# V2_Layout.net
KiCad netlist of a schematic drawn in EAGLE
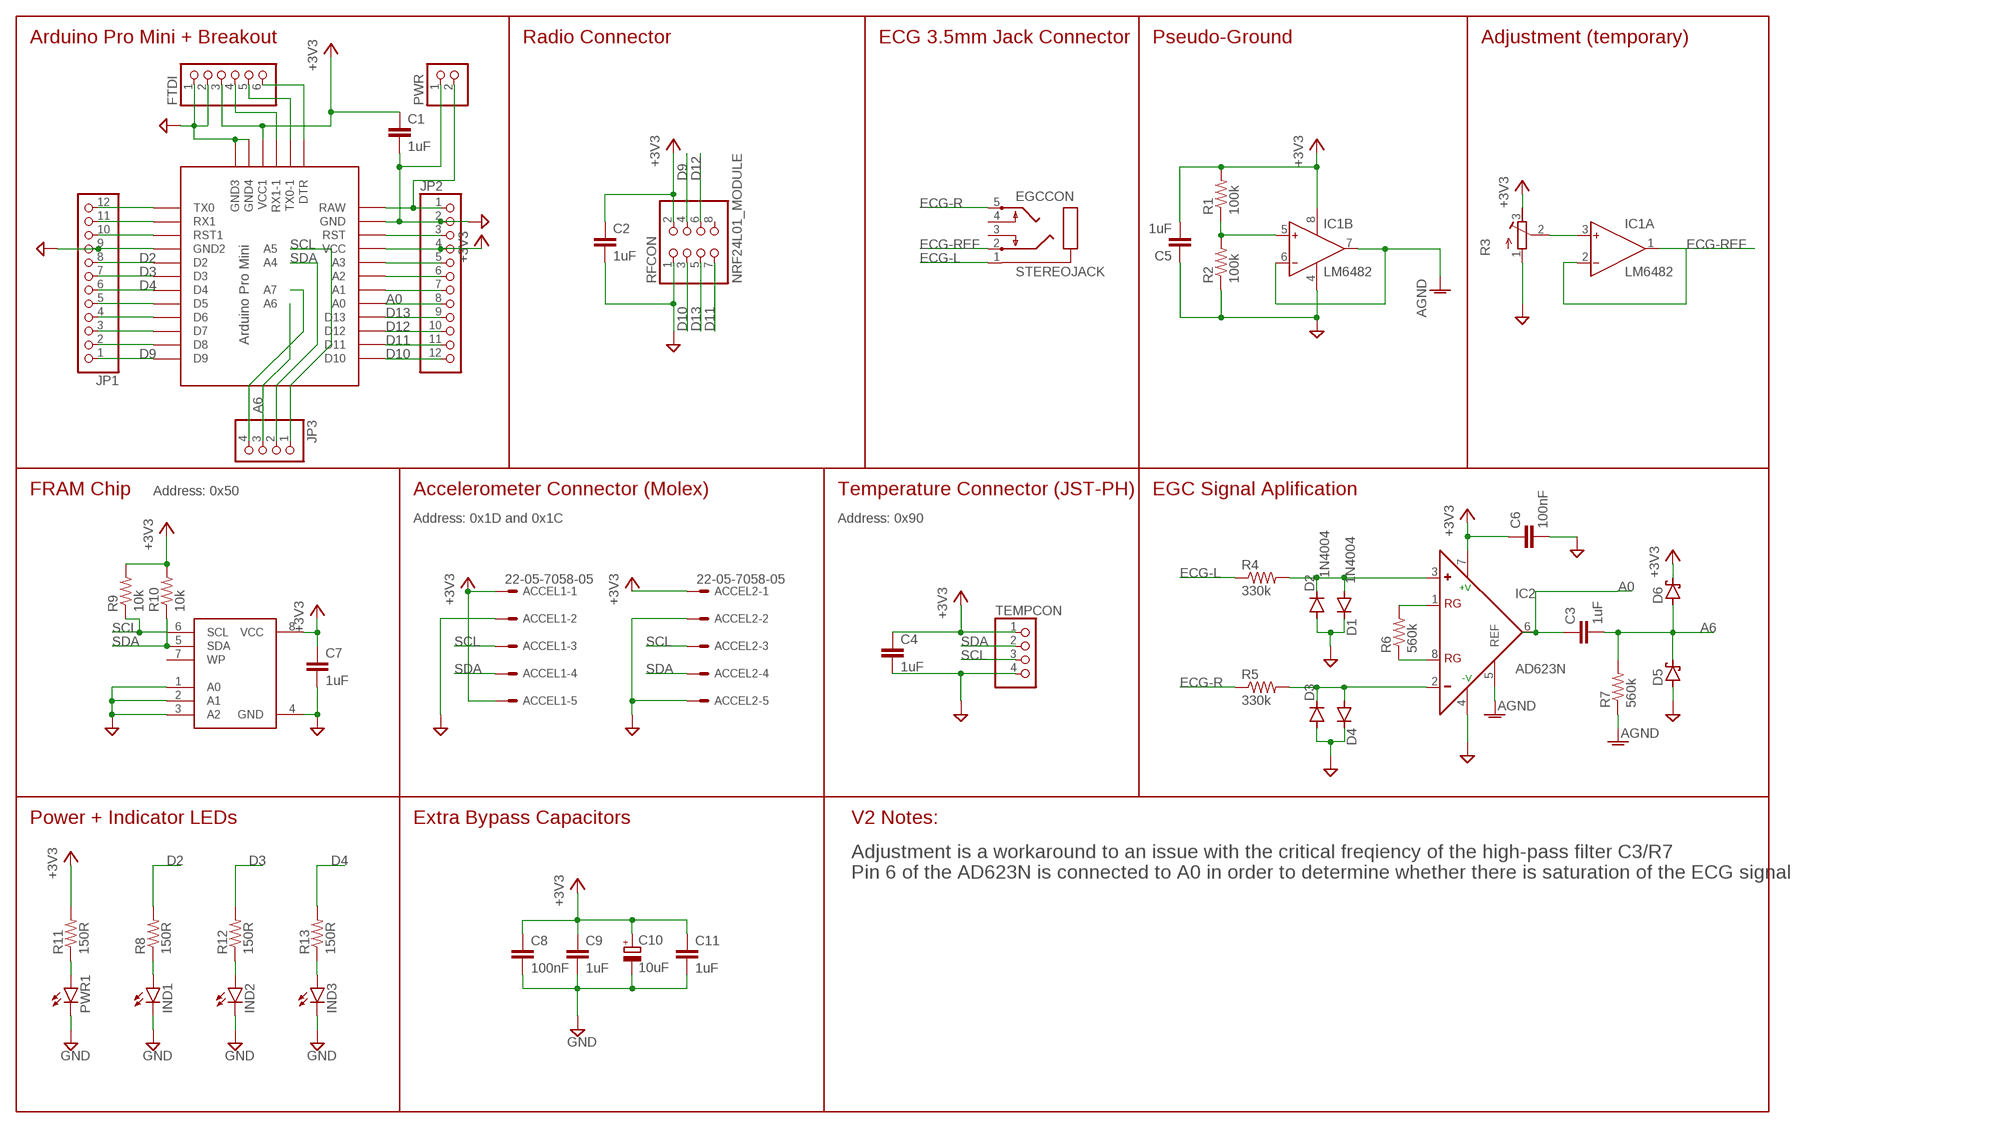
[diagram p0: schematic, sheet 1]

(export (version "E")
  (design (tool "Eeschema 10.0.6"))
  (components
    (comp (ref "ACCEL1")
      (value "22-05-7058-05")
      (footprint "eagle-import:7395-05")
      (fields (field (name "MF") "MOLEX"))
      (libsource (lib "eagle-import") (part "22-?-0505-7058"))
    )
    (comp (ref "ACCEL2")
      (value "22-05-7058-05")
      (footprint "eagle-import:7395-05")
      (fields (field (name "MF") "MOLEX"))
      (libsource (lib "eagle-import") (part "22-?-0505-7058"))
    )
    (comp (ref "C1")
      (value "1uF")
      (footprint "eagle-import:C0603")
      (libsource (lib "eagle-import") (part "C-EUC0603"))
    )
    (comp (ref "C2")
      (value "1uF")
      (footprint "eagle-import:C0603")
      (libsource (lib "eagle-import") (part "C-EUC0603"))
    )
    (comp (ref "C3")
      (value "1uF")
      (footprint "eagle-import:C0603")
      (libsource (lib "eagle-import") (part "C-EUC0603"))
    )
    (comp (ref "C4")
      (value "1uF")
      (footprint "eagle-import:C0603")
      (libsource (lib "eagle-import") (part "C-EUC0603"))
    )
    (comp (ref "C5")
      (value "1uF")
      (footprint "eagle-import:C0603")
      (libsource (lib "eagle-import") (part "C-EUC0603"))
    )
    (comp (ref "C6")
      (value "100nF")
      (footprint "eagle-import:C0603")
      (libsource (lib "eagle-import") (part "C-EUC0603"))
    )
    (comp (ref "C7")
      (value "1uF")
      (footprint "eagle-import:C0603")
      (libsource (lib "eagle-import") (part "C-EUC0603"))
    )
    (comp (ref "C8")
      (value "100nF")
      (footprint "eagle-import:C025-030X050")
      (libsource (lib "eagle-import") (part "C-EU025-030X050"))
    )
    (comp (ref "C9")
      (value "1uF")
      (footprint "eagle-import:C025-030X050")
      (libsource (lib "eagle-import") (part "C-EU025-030X050"))
    )
    (comp (ref "C10")
      (value "10uF")
      (footprint "eagle-import:TAP5-45")
      (libsource (lib "eagle-import") (part "CPOL-EUTAP5-45"))
    )
    (comp (ref "C11")
      (value "1uF")
      (footprint "eagle-import:C025-030X050")
      (libsource (lib "eagle-import") (part "C-EU025-030X050"))
    )
    (comp (ref "D1")
      (value "1N4004")
      (footprint "eagle-import:DO41-10")
      (libsource (lib "eagle-import") (part "1N4004"))
    )
    (comp (ref "D2")
      (value "1N4004")
      (footprint "eagle-import:DO41-10")
      (libsource (lib "eagle-import") (part "1N4004"))
    )
    (comp (ref "D3")
      (value "1N4004")
      (footprint "eagle-import:DO41-10")
      (libsource (lib "eagle-import") (part "1N4004"))
    )
    (comp (ref "D4")
      (value "1N4004")
      (footprint "eagle-import:DO41-10")
      (libsource (lib "eagle-import") (part "1N4004"))
    )
    (comp (ref "D5")
      (value "SCHOTTKY-DIODEDO35-7")
      (footprint "eagle-import:DO35-7")
      (libsource (lib "eagle-import") (part "SCHOTTKY-DIODEDO35-7"))
    )
    (comp (ref "D6")
      (value "SCHOTTKY-DIODEDO35-7")
      (footprint "eagle-import:DO35-7")
      (libsource (lib "eagle-import") (part "SCHOTTKY-DIODEDO35-7"))
    )
    (comp (ref "EGCCON")
      (value "STEREOJACK")
      (footprint "eagle-import:STX3100")
      (libsource (lib "eagle-import") (part "STEREOJACK"))
    )
    (comp (ref "FTDI")
      (value "PINHD-1X6")
      (footprint "eagle-import:1X06")
      (libsource (lib "eagle-import") (part "PINHD-1X6"))
    )
    (comp (ref "IC1")
      (value "LM6482")
      (footprint "eagle-import:DIL08")
      (fields (field (name "MF") "ALTERA CORPORATION") (field (name "MPN") "AD826ANZ"))
      (libsource (lib "eagle-import") (part "AD826N"))
    )
    (comp (ref "IC2")
      (value "AD623N")
      (footprint "eagle-import:DIL08")
      (fields (field (name "MF") "ALTERA CORPORATION") (field (name "MPN") "AD623ANZ"))
      (libsource (lib "eagle-import") (part "AD623N"))
    )
    (comp (ref "IND1")
      (value "LEDCHIPLED_0805")
      (footprint "eagle-import:CHIPLED_0805")
      (libsource (lib "eagle-import") (part "LEDCHIPLED_0805"))
    )
    (comp (ref "IND2")
      (value "LEDCHIPLED_0805")
      (footprint "eagle-import:CHIPLED_0805")
      (libsource (lib "eagle-import") (part "LEDCHIPLED_0805"))
    )
    (comp (ref "IND3")
      (value "LEDCHIPLED_0805")
      (footprint "eagle-import:CHIPLED_0805")
      (libsource (lib "eagle-import") (part "LEDCHIPLED_0805"))
    )
    (comp (ref "JP1")
      (value "PINHD-1X12")
      (footprint "eagle-import:1X12")
      (libsource (lib "eagle-import") (part "PINHD-1X12"))
    )
    (comp (ref "JP2")
      (value "PINHD-1X12")
      (footprint "eagle-import:1X12")
      (libsource (lib "eagle-import") (part "PINHD-1X12"))
    )
    (comp (ref "JP3")
      (value "PINHD-1X4")
      (footprint "eagle-import:1X04")
      (libsource (lib "eagle-import") (part "pinhead_325_PINHD-1X4"))
    )
    (comp (ref "PWR")
      (value "PINHD-1X2")
      (footprint "eagle-import:1X02")
      (libsource (lib "eagle-import") (part "PINHD-1X2"))
    )
    (comp (ref "PWR1")
      (value "LEDCHIPLED_0805")
      (footprint "eagle-import:CHIPLED_0805")
      (libsource (lib "eagle-import") (part "LEDCHIPLED_0805"))
    )
    (comp (ref "R1")
      (value "100k")
      (footprint "eagle-import:R0603")
      (libsource (lib "eagle-import") (part "R-US_R0603"))
    )
    (comp (ref "R2")
      (value "100k")
      (footprint "eagle-import:R0603")
      (libsource (lib "eagle-import") (part "R-US_R0603"))
    )
    (comp (ref "R3")
      (value "R-TRIMM64P")
      (footprint "eagle-import:RTRIM64P")
      (libsource (lib "eagle-import") (part "R-TRIMM64P"))
    )
    (comp (ref "R4")
      (value "330k")
      (footprint "eagle-import:R0603")
      (libsource (lib "eagle-import") (part "R-US_R0603"))
    )
    (comp (ref "R5")
      (value "330k")
      (footprint "eagle-import:R0603")
      (libsource (lib "eagle-import") (part "R-US_R0603"))
    )
    (comp (ref "R6")
      (value "560k")
      (footprint "eagle-import:R0603")
      (libsource (lib "eagle-import") (part "R-US_R0603"))
    )
    (comp (ref "R7")
      (value "560k")
      (footprint "eagle-import:R0603")
      (libsource (lib "eagle-import") (part "R-US_R0603"))
    )
    (comp (ref "R8")
      (value "150R")
      (footprint "eagle-import:R0603")
      (libsource (lib "eagle-import") (part "R-US_R0603"))
    )
    (comp (ref "R9")
      (value "10k")
      (footprint "eagle-import:R0603")
      (libsource (lib "eagle-import") (part "R-US_R0603"))
    )
    (comp (ref "R10")
      (value "10k")
      (footprint "eagle-import:R0603")
      (libsource (lib "eagle-import") (part "R-US_R0603"))
    )
    (comp (ref "R11")
      (value "150R")
      (footprint "eagle-import:R0603")
      (libsource (lib "eagle-import") (part "R-US_R0603"))
    )
    (comp (ref "R12")
      (value "150R")
      (footprint "eagle-import:R0603")
      (libsource (lib "eagle-import") (part "R-US_R0603"))
    )
    (comp (ref "R13")
      (value "150R")
      (footprint "eagle-import:R0603")
      (libsource (lib "eagle-import") (part "R-US_R0603"))
    )
    (comp (ref "RFCON")
      (value "NRF24L01_MODULE")
      (footprint "eagle-import:2X04")
      (libsource (lib "eagle-import") (part "NRF24L01_MODULE"))
    )
    (comp (ref "TEMPCON")
      (value "PINHD-1X4M")
      (footprint "eagle-import:1X04M")
      (libsource (lib "eagle-import") (part "PINHD-1X4M"))
    )
    (comp (ref "U$1")
      (value "PRO-MINI-2")
      (footprint "eagle-import:PRO-MINI-2")
      (libsource (lib "eagle-import") (part "PRO-MINI-2"))
    )
    (comp (ref "U2")
      (value "MB85RC256VPF-G-JNERE2")
      (footprint "eagle-import:SOIC8")
      (libsource (lib "eagle-import") (part "MB85RC256VPF-G-JNERE2"))
    )
  )
  (nets
    (net (code "1") (name "+3V3") (class "Default")
      (node (ref "ACCEL1") (pin "1") (pinfunction "S_1") (pintype "passive"))
      (node (ref "ACCEL1") (pin "5") (pinfunction "S_5") (pintype "passive"))
      (node (ref "ACCEL2") (pin "1") (pinfunction "S_1") (pintype "passive"))
      (node (ref "C1") (pin "1") (pinfunction "1_1") (pintype "passive"))
      (node (ref "C10") (pin "+") (pinfunction "+_+") (pintype "passive"))
      (node (ref "C11") (pin "1") (pinfunction "1_1") (pintype "passive"))
      (node (ref "C2") (pin "1") (pinfunction "1_1") (pintype "passive"))
      (node (ref "C4") (pin "1") (pinfunction "1_1") (pintype "passive"))
      (node (ref "C5") (pin "2") (pinfunction "2_2") (pintype "passive"))
      (node (ref "C6") (pin "1") (pinfunction "1_1") (pintype "passive"))
      (node (ref "C7") (pin "1") (pinfunction "1_1") (pintype "passive"))
      (node (ref "C8") (pin "1") (pinfunction "1_1") (pintype "passive"))
      (node (ref "C9") (pin "1") (pinfunction "1_1") (pintype "passive"))
      (node (ref "D6") (pin "C") (pinfunction "C_C") (pintype "passive"))
      (node (ref "FTDI") (pin "3") (pinfunction "3_3") (pintype "passive"))
      (node (ref "IC1") (pin "8") (pinfunction "V+_8") (pintype "power_in"))
      (node (ref "IC2") (pin "7") (pinfunction "+V_7") (pintype "power_in"))
      (node (ref "JP2") (pin "4") (pinfunction "4_4") (pintype "passive"))
      (node (ref "R1") (pin "2") (pinfunction "2_2") (pintype "passive"))
      (node (ref "R10") (pin "2") (pinfunction "2_2") (pintype "passive"))
      (node (ref "R11") (pin "2") (pinfunction "2_2") (pintype "passive"))
      (node (ref "R3") (pin "3") (pinfunction "E_3") (pintype "passive"))
      (node (ref "R9") (pin "2") (pinfunction "2_2") (pintype "passive"))
      (node (ref "RFCON") (pin "2") (pinfunction "2_2") (pintype "passive"))
      (node (ref "TEMPCON") (pin "1") (pinfunction "1_1") (pintype "passive"))
      (node (ref "U$1") (pin "VCC") (pinfunction "VCC_VCC") (pintype "bidirectional"))
      (node (ref "U$1") (pin "VCC1") (pinfunction "VCC1_VCC1") (pintype "bidirectional"))
      (node (ref "U2") (pin "8") (pinfunction "VCC_8") (pintype "bidirectional"))
    )
    (net (code "2") (name "/A0") (class "Default")
      (node (ref "C3") (pin "1") (pinfunction "1_1") (pintype "passive"))
      (node (ref "IC2") (pin "6") (pinfunction "OUT_6") (pintype "output"))
      (node (ref "JP2") (pin "8") (pinfunction "8_8") (pintype "passive"))
      (node (ref "U$1") (pin "A3") (pinfunction "A0_A3") (pintype "bidirectional"))
    )
    (net (code "3") (name "/A6") (class "Default")
      (node (ref "C3") (pin "2") (pinfunction "2_2") (pintype "passive"))
      (node (ref "D5") (pin "C") (pinfunction "C_C") (pintype "passive"))
      (node (ref "D6") (pin "A") (pinfunction "A_A") (pintype "passive"))
      (node (ref "JP3") (pin "3") (pinfunction "3_3") (pintype "passive"))
      (node (ref "R7") (pin "2") (pinfunction "2_2") (pintype "passive"))
      (node (ref "U$1") (pin "A6") (pinfunction "A6_A6") (pintype "bidirectional"))
    )
    (net (code "4") (name "/D2") (class "Default")
      (node (ref "JP1") (pin "8") (pinfunction "8_8") (pintype "passive"))
      (node (ref "R8") (pin "2") (pinfunction "2_2") (pintype "passive"))
      (node (ref "U$1") (pin "D2") (pinfunction "D2_D2") (pintype "bidirectional"))
    )
    (net (code "5") (name "/D3") (class "Default")
      (node (ref "JP1") (pin "7") (pinfunction "7_7") (pintype "passive"))
      (node (ref "R12") (pin "2") (pinfunction "2_2") (pintype "passive"))
      (node (ref "U$1") (pin "D3") (pinfunction "D3_D3") (pintype "bidirectional"))
    )
    (net (code "6") (name "/D4") (class "Default")
      (node (ref "JP1") (pin "6") (pinfunction "6_6") (pintype "passive"))
      (node (ref "R13") (pin "2") (pinfunction "2_2") (pintype "passive"))
      (node (ref "U$1") (pin "D4") (pinfunction "D4_D4") (pintype "bidirectional"))
    )
    (net (code "7") (name "/D9") (class "Default")
      (node (ref "JP1") (pin "1") (pinfunction "1_1") (pintype "passive"))
      (node (ref "RFCON") (pin "4") (pinfunction "4_4") (pintype "passive"))
      (node (ref "U$1") (pin "D9") (pinfunction "D9_D9") (pintype "bidirectional"))
    )
    (net (code "8") (name "/D10") (class "Default")
      (node (ref "JP2") (pin "12") (pinfunction "12_12") (pintype "passive"))
      (node (ref "RFCON") (pin "3") (pinfunction "3_3") (pintype "passive"))
      (node (ref "U$1") (pin "D10") (pinfunction "D10_D10") (pintype "bidirectional"))
    )
    (net (code "9") (name "/D11") (class "Default")
      (node (ref "JP2") (pin "11") (pinfunction "11_11") (pintype "passive"))
      (node (ref "RFCON") (pin "7") (pinfunction "7_7") (pintype "passive"))
      (node (ref "U$1") (pin "D11") (pinfunction "D11_D11") (pintype "bidirectional"))
    )
    (net (code "10") (name "/D12") (class "Default")
      (node (ref "JP2") (pin "10") (pinfunction "10_10") (pintype "passive"))
      (node (ref "RFCON") (pin "6") (pinfunction "6_6") (pintype "passive"))
      (node (ref "U$1") (pin "D12") (pinfunction "D12_D12") (pintype "bidirectional"))
    )
    (net (code "11") (name "/D13") (class "Default")
      (node (ref "JP2") (pin "9") (pinfunction "9_9") (pintype "passive"))
      (node (ref "RFCON") (pin "5") (pinfunction "5_5") (pintype "passive"))
      (node (ref "U$1") (pin "D13") (pinfunction "D13_D13") (pintype "bidirectional"))
    )
    (net (code "12") (name "/ECG-L") (class "Default")
      (node (ref "EGCCON") (pin "1") (pinfunction "1_1") (pintype "passive"))
      (node (ref "R4") (pin "1") (pinfunction "1_1") (pintype "passive"))
    )
    (net (code "13") (name "/ECG-R") (class "Default")
      (node (ref "EGCCON") (pin "5") (pinfunction "5_5") (pintype "passive"))
      (node (ref "R5") (pin "1") (pinfunction "1_1") (pintype "passive"))
    )
    (net (code "14") (name "/ECG-REF") (class "Default")
      (node (ref "EGCCON") (pin "2") (pinfunction "2_2") (pintype "passive"))
      (node (ref "IC1") (pin "1") (pinfunction "OUT_1") (pintype "output"))
      (node (ref "IC1") (pin "2") (pinfunction "IN-_2") (pintype "input"))
    )
    (net (code "15") (name "/SCL") (class "Default")
      (node (ref "ACCEL1") (pin "3") (pinfunction "S_3") (pintype "passive"))
      (node (ref "ACCEL2") (pin "3") (pinfunction "S_3") (pintype "passive"))
      (node (ref "JP3") (pin "1") (pinfunction "1_1") (pintype "passive"))
      (node (ref "R9") (pin "1") (pinfunction "1_1") (pintype "passive"))
      (node (ref "TEMPCON") (pin "3") (pinfunction "3_3") (pintype "passive"))
      (node (ref "U$1") (pin "A5") (pinfunction "A5_A5") (pintype "bidirectional"))
      (node (ref "U2") (pin "6") (pinfunction "SCL_6") (pintype "bidirectional"))
    )
    (net (code "16") (name "/SDA") (class "Default")
      (node (ref "ACCEL1") (pin "4") (pinfunction "S_4") (pintype "passive"))
      (node (ref "ACCEL2") (pin "4") (pinfunction "S_4") (pintype "passive"))
      (node (ref "JP3") (pin "2") (pinfunction "2_2") (pintype "passive"))
      (node (ref "R10") (pin "1") (pinfunction "1_1") (pintype "passive"))
      (node (ref "TEMPCON") (pin "2") (pinfunction "2_2") (pintype "passive"))
      (node (ref "U$1") (pin "A4") (pinfunction "A4_A4") (pintype "bidirectional"))
      (node (ref "U2") (pin "5") (pinfunction "SDA_5") (pintype "bidirectional"))
    )
    (net (code "17") (name "AGND") (class "Default")
      (node (ref "IC1") (pin "6") (pinfunction "IN-_6") (pintype "input"))
      (node (ref "IC1") (pin "7") (pinfunction "OUT_7") (pintype "output"))
      (node (ref "IC2") (pin "5") (pinfunction "REF_5") (pintype "passive"))
      (node (ref "R7") (pin "1") (pinfunction "1_1") (pintype "passive"))
    )
    (net (code "18") (name "GND") (class "Default")
      (node (ref "ACCEL1") (pin "2") (pinfunction "S_2") (pintype "passive"))
      (node (ref "ACCEL2") (pin "2") (pinfunction "S_2") (pintype "passive"))
      (node (ref "ACCEL2") (pin "5") (pinfunction "S_5") (pintype "passive"))
      (node (ref "C1") (pin "2") (pinfunction "2_2") (pintype "passive"))
      (node (ref "C10") (pin "-") (pinfunction "-_-") (pintype "passive"))
      (node (ref "C11") (pin "2") (pinfunction "2_2") (pintype "passive"))
      (node (ref "C2") (pin "2") (pinfunction "2_2") (pintype "passive"))
      (node (ref "C4") (pin "2") (pinfunction "2_2") (pintype "passive"))
      (node (ref "C5") (pin "1") (pinfunction "1_1") (pintype "passive"))
      (node (ref "C6") (pin "2") (pinfunction "2_2") (pintype "passive"))
      (node (ref "C7") (pin "2") (pinfunction "2_2") (pintype "passive"))
      (node (ref "C8") (pin "2") (pinfunction "2_2") (pintype "passive"))
      (node (ref "C9") (pin "2") (pinfunction "2_2") (pintype "passive"))
      (node (ref "D1") (pin "C") (pinfunction "C_C") (pintype "passive"))
      (node (ref "D2") (pin "A") (pinfunction "A_A") (pintype "passive"))
      (node (ref "D3") (pin "A") (pinfunction "A_A") (pintype "passive"))
      (node (ref "D4") (pin "C") (pinfunction "C_C") (pintype "passive"))
      (node (ref "D5") (pin "A") (pinfunction "A_A") (pintype "passive"))
      (node (ref "FTDI") (pin "1") (pinfunction "1_1") (pintype "passive"))
      (node (ref "FTDI") (pin "2") (pinfunction "2_2") (pintype "passive"))
      (node (ref "IC1") (pin "4") (pinfunction "V-_4") (pintype "power_in"))
      (node (ref "IC2") (pin "4") (pinfunction "-V_4") (pintype "power_in"))
      (node (ref "IND1") (pin "C") (pinfunction "C_C") (pintype "passive"))
      (node (ref "IND2") (pin "C") (pinfunction "C_C") (pintype "passive"))
      (node (ref "IND3") (pin "C") (pinfunction "C_C") (pintype "passive"))
      (node (ref "JP1") (pin "9") (pinfunction "9_9") (pintype "passive"))
      (node (ref "JP2") (pin "2") (pinfunction "2_2") (pintype "passive"))
      (node (ref "PWR") (pin "1") (pinfunction "1_1") (pintype "passive"))
      (node (ref "PWR1") (pin "C") (pinfunction "C_C") (pintype "passive"))
      (node (ref "R2") (pin "1") (pinfunction "1_1") (pintype "passive"))
      (node (ref "R3") (pin "1") (pinfunction "A_1") (pintype "passive"))
      (node (ref "RFCON") (pin "1") (pinfunction "1_1") (pintype "passive"))
      (node (ref "TEMPCON") (pin "4") (pinfunction "4_4") (pintype "passive"))
      (node (ref "U$1") (pin "GND") (pinfunction "GND_GND") (pintype "bidirectional"))
      (node (ref "U$1") (pin "GND1") (pinfunction "GND2_GND1") (pintype "bidirectional"))
      (node (ref "U$1") (pin "GND2") (pinfunction "GND3_GND2") (pintype "bidirectional"))
      (node (ref "U$1") (pin "GND3") (pinfunction "GND4_GND3") (pintype "bidirectional"))
      (node (ref "U2") (pin "1") (pinfunction "A0_1") (pintype "bidirectional"))
      (node (ref "U2") (pin "2") (pinfunction "A1_2") (pintype "bidirectional"))
      (node (ref "U2") (pin "3") (pinfunction "A2_3") (pintype "bidirectional"))
      (node (ref "U2") (pin "4") (pinfunction "GND_4") (pintype "bidirectional"))
    )
    (net (code "19") (name "Net-(FTDI-Pad4)") (class "Default")
      (node (ref "FTDI") (pin "4") (pinfunction "4_4") (pintype "passive"))
      (node (ref "U$1") (pin "RX1-1") (pinfunction "RX1-1_RX1-1") (pintype "bidirectional"))
    )
    (net (code "20") (name "Net-(FTDI-Pad5)") (class "Default")
      (node (ref "FTDI") (pin "5") (pinfunction "5_5") (pintype "passive"))
      (node (ref "U$1") (pin "TX0-1") (pinfunction "TX0-1_TX0-1") (pintype "bidirectional"))
    )
    (net (code "21") (name "Net-(FTDI-Pad6)") (class "Default")
      (node (ref "FTDI") (pin "6") (pinfunction "6_6") (pintype "passive"))
      (node (ref "U$1") (pin "DTR") (pinfunction "DTR_DTR") (pintype "bidirectional"))
    )
    (net (code "22") (name "Net-(IC1A-IN+)") (class "Default")
      (node (ref "IC1") (pin "3") (pinfunction "IN+_3") (pintype "input"))
      (node (ref "R3") (pin "2") (pinfunction "S_2") (pintype "passive"))
    )
    (net (code "23") (name "Net-(IC1B-IN+)") (class "Default")
      (node (ref "IC1") (pin "5") (pinfunction "IN+_5") (pintype "input"))
      (node (ref "R1") (pin "1") (pinfunction "1_1") (pintype "passive"))
      (node (ref "R2") (pin "2") (pinfunction "2_2") (pintype "passive"))
    )
    (net (code "24") (name "Net-(IC2-+)") (class "Default")
      (node (ref "D1") (pin "A") (pinfunction "A_A") (pintype "passive"))
      (node (ref "D2") (pin "C") (pinfunction "C_C") (pintype "passive"))
      (node (ref "IC2") (pin "3") (pinfunction "+_3") (pintype "input"))
      (node (ref "R4") (pin "2") (pinfunction "2_2") (pintype "passive"))
    )
    (net (code "25") (name "Net-(IC2--)") (class "Default")
      (node (ref "D3") (pin "C") (pinfunction "C_C") (pintype "passive"))
      (node (ref "D4") (pin "A") (pinfunction "A_A") (pintype "passive"))
      (node (ref "IC2") (pin "2") (pinfunction "-_2") (pintype "input"))
      (node (ref "R5") (pin "2") (pinfunction "2_2") (pintype "passive"))
    )
    (net (code "26") (name "Net-(IC2-RG-Pad1)") (class "Default")
      (node (ref "IC2") (pin "1") (pinfunction "RG_1") (pintype "passive"))
      (node (ref "R6") (pin "2") (pinfunction "2_2") (pintype "passive"))
    )
    (net (code "27") (name "Net-(IC2-RG-Pad8)") (class "Default")
      (node (ref "IC2") (pin "8") (pinfunction "RG_8") (pintype "passive"))
      (node (ref "R6") (pin "1") (pinfunction "1_1") (pintype "passive"))
    )
    (net (code "28") (name "Net-(IND1-PadA)") (class "Default")
      (node (ref "IND1") (pin "A") (pinfunction "A_A") (pintype "passive"))
      (node (ref "R8") (pin "1") (pinfunction "1_1") (pintype "passive"))
    )
    (net (code "29") (name "Net-(IND2-PadA)") (class "Default")
      (node (ref "IND2") (pin "A") (pinfunction "A_A") (pintype "passive"))
      (node (ref "R12") (pin "1") (pinfunction "1_1") (pintype "passive"))
    )
    (net (code "30") (name "Net-(IND3-PadA)") (class "Default")
      (node (ref "IND3") (pin "A") (pinfunction "A_A") (pintype "passive"))
      (node (ref "R13") (pin "1") (pinfunction "1_1") (pintype "passive"))
    )
    (net (code "31") (name "Net-(JP1-Pad2)") (class "Default")
      (node (ref "JP1") (pin "2") (pinfunction "2_2") (pintype "passive"))
      (node (ref "U$1") (pin "D8") (pinfunction "D8_D8") (pintype "bidirectional"))
    )
    (net (code "32") (name "Net-(JP1-Pad3)") (class "Default")
      (node (ref "JP1") (pin "3") (pinfunction "3_3") (pintype "passive"))
      (node (ref "U$1") (pin "D7") (pinfunction "D7_D7") (pintype "bidirectional"))
    )
    (net (code "33") (name "Net-(JP1-Pad4)") (class "Default")
      (node (ref "JP1") (pin "4") (pinfunction "4_4") (pintype "passive"))
      (node (ref "U$1") (pin "D6") (pinfunction "D6_D6") (pintype "bidirectional"))
    )
    (net (code "34") (name "Net-(JP1-Pad5)") (class "Default")
      (node (ref "JP1") (pin "5") (pinfunction "5_5") (pintype "passive"))
      (node (ref "U$1") (pin "D5") (pinfunction "D5_D5") (pintype "bidirectional"))
    )
    (net (code "35") (name "Net-(JP1-Pad10)") (class "Default")
      (node (ref "JP1") (pin "10") (pinfunction "10_10") (pintype "passive"))
      (node (ref "U$1") (pin "RST1") (pinfunction "RST1_RST1") (pintype "bidirectional"))
    )
    (net (code "36") (name "Net-(JP1-Pad11)") (class "Default")
      (node (ref "JP1") (pin "11") (pinfunction "11_11") (pintype "passive"))
      (node (ref "U$1") (pin "RX1") (pinfunction "RX1_RX1") (pintype "bidirectional"))
    )
    (net (code "37") (name "Net-(JP1-Pad12)") (class "Default")
      (node (ref "JP1") (pin "12") (pinfunction "12_12") (pintype "passive"))
      (node (ref "U$1") (pin "TX0") (pinfunction "TX0_TX0") (pintype "bidirectional"))
    )
    (net (code "38") (name "Net-(JP2-Pad1)") (class "Default")
      (node (ref "JP2") (pin "1") (pinfunction "1_1") (pintype "passive"))
      (node (ref "PWR") (pin "2") (pinfunction "2_2") (pintype "passive"))
      (node (ref "U$1") (pin "RAW") (pinfunction "RAW_RAW") (pintype "bidirectional"))
    )
    (net (code "39") (name "Net-(JP2-Pad3)") (class "Default")
      (node (ref "JP2") (pin "3") (pinfunction "3_3") (pintype "passive"))
      (node (ref "U$1") (pin "RST") (pinfunction "RST_RST") (pintype "bidirectional"))
    )
    (net (code "40") (name "Net-(JP3-Pad4)") (class "Default")
      (node (ref "JP3") (pin "4") (pinfunction "4_4") (pintype "passive"))
      (node (ref "U$1") (pin "A7") (pinfunction "A7_A7") (pintype "bidirectional"))
    )
    (net (code "41") (name "Net-(PWR1-PadA)") (class "Default")
      (node (ref "PWR1") (pin "A") (pinfunction "A_A") (pintype "passive"))
      (node (ref "R11") (pin "1") (pinfunction "1_1") (pintype "passive"))
    )
    (net (code "42") (name "Net-(U$1-A1)") (class "Default")
      (node (ref "JP2") (pin "7") (pinfunction "7_7") (pintype "passive"))
      (node (ref "U$1") (pin "A2") (pinfunction "A1_A2") (pintype "bidirectional"))
    )
    (net (code "43") (name "Net-(U$1-A2)") (class "Default")
      (node (ref "JP2") (pin "6") (pinfunction "6_6") (pintype "passive"))
      (node (ref "U$1") (pin "A1") (pinfunction "A2_A1") (pintype "bidirectional"))
    )
    (net (code "44") (name "Net-(U$1-A3)") (class "Default")
      (node (ref "JP2") (pin "5") (pinfunction "5_5") (pintype "passive"))
      (node (ref "U$1") (pin "A0") (pinfunction "A3_A0") (pintype "bidirectional"))
    )
    (net (code "45") (name "unconnected-(EGCCON-Pad3)") (class "Default")
      (node (ref "EGCCON") (pin "3") (pinfunction "3_3") (pintype "passive"))
    )
    (net (code "46") (name "unconnected-(EGCCON-Pad4)") (class "Default")
      (node (ref "EGCCON") (pin "4") (pinfunction "4_4") (pintype "passive"))
    )
    (net (code "47") (name "unconnected-(RFCON-Pad8)") (class "Default")
      (node (ref "RFCON") (pin "8") (pinfunction "8_8") (pintype "passive"))
    )
    (net (code "48") (name "unconnected-(U2-WP-Pad7)") (class "Default")
      (node (ref "U2") (pin "7") (pinfunction "WP_7") (pintype "bidirectional"))
    )
  )
)
